# PWM_Regenerator.net
KiCad netlist of a schematic drawn in Altium Designer
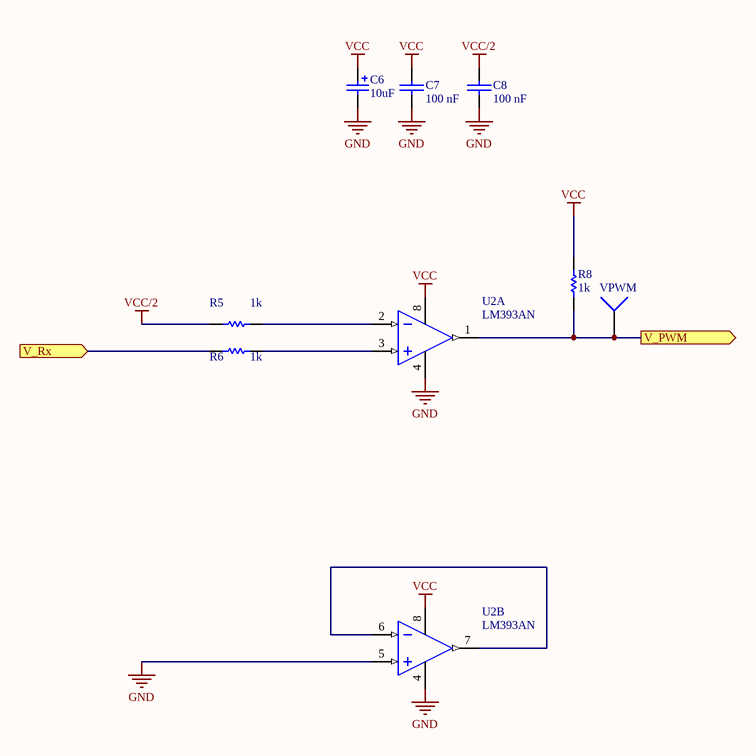
[diagram p0: PWM Regenerator.SchDoc]

(export (version "E")
  (design (tool "Eeschema 10.0.6"))
  (components
    (comp (ref "C6")
      (value "10uF")
      (footprint "ece-CAPAD2TH0.3")
      (description "Polarized Capacitor (Radial)")
      (fields (field (name "MANUFACTURER") "Generic Components") (field (name "PUBLISHER") "Altium Limited"))
      (libsource (lib "ece components") (part "CAP 22uF TH"))
    )
    (comp (ref "C7")
      (value "100 nF")
      (footprint "ece-RAD0.2")
      (description "Capacitor Non Polarised Through Hole")
      (libsource (lib "ece components") (part "CAP"))
    )
    (comp (ref "C8")
      (value "100 nF")
      (footprint "ece-RAD0.2")
      (description "Capacitor Non Polarised Through Hole")
      (libsource (lib "ece components") (part "CAP"))
    )
    (comp (ref "R5")
      (value "1k")
      (footprint "ece-AXIAL0.4")
      (description "Resistor")
      (fields (field (name "PUBLISHER") "Altium Limited"))
      (libsource (lib "ece components") (part "Res1"))
    )
    (comp (ref "R6")
      (value "1k")
      (footprint "ece-AXIAL0.4")
      (description "Resistor")
      (fields (field (name "PUBLISHER") "Altium Limited"))
      (libsource (lib "ece components") (part "Res1"))
    )
    (comp (ref "R8")
      (value "1k")
      (footprint "ece-AXIAL0.4")
      (description "Resistor")
      (fields (field (name "PUBLISHER") "Altium Limited"))
      (libsource (lib "ece components") (part "Res1"))
    )
    (comp (ref "U2")
      (value "LM393AN")
      (footprint "ECE-DIP8")
      (description "Dual Comparator")
      (fields (field (name "PUBLISHER") "Altium Limited"))
      (libsource (lib "ece components") (part "LM393AN"))
    )
    (comp (ref "VPWM")
      (value "VPWM")
      (footprint "ece-HDR1")
      (description "Socket")
      (fields (field (name "PUBLISHER") "Altium Limited"))
      (libsource (lib "ece components") (part "Test pin"))
    )
  )
  (nets
    (net (code "1") (name "/V_PWM") (class "Default")
      (node (ref "R8") (pin "1") (pinfunction "1_1") (pintype "passive"))
      (node (ref "U2") (pin "1") (pinfunction "OUT_1") (pintype "output"))
      (node (ref "VPWM") (pin "1") (pinfunction "1_1") (pintype "passive"))
    )
    (net (code "2") (name "/V_Rx") (class "Default")
      (node (ref "R6") (pin "1") (pinfunction "1_1") (pintype "passive"))
    )
    (net (code "3") (name "GND") (class "Default")
      (node (ref "C6") (pin "2") (pinfunction "2_2") (pintype "passive"))
      (node (ref "C7") (pin "2") (pinfunction "2_2") (pintype "passive"))
      (node (ref "C8") (pin "2") (pinfunction "2_2") (pintype "passive"))
      (node (ref "U2") (pin "4") (pinfunction "GND_4") (pintype "power_in"))
      (node (ref "U2") (pin "5") (pinfunction "IN+_5") (pintype "input"))
    )
    (net (code "4") (name "Net-(U2A-IN+)") (class "Default")
      (node (ref "R6") (pin "2") (pinfunction "2_2") (pintype "passive"))
      (node (ref "U2") (pin "3") (pinfunction "IN+_3") (pintype "input"))
    )
    (net (code "5") (name "Net-(U2A-IN-)") (class "Default")
      (node (ref "R5") (pin "2") (pinfunction "2_2") (pintype "passive"))
      (node (ref "U2") (pin "2") (pinfunction "IN-_2") (pintype "input"))
    )
    (net (code "6") (name "Net-(U2B-IN-)") (class "Default")
      (node (ref "U2") (pin "6") (pinfunction "IN-_6") (pintype "input"))
      (node (ref "U2") (pin "7") (pinfunction "OUT_7") (pintype "output"))
    )
    (net (code "7") (name "VCC") (class "Default")
      (node (ref "C6") (pin "1") (pinfunction "1_1") (pintype "passive"))
      (node (ref "C7") (pin "1") (pinfunction "1_1") (pintype "passive"))
      (node (ref "R8") (pin "2") (pinfunction "2_2") (pintype "passive"))
      (node (ref "U2") (pin "8") (pinfunction "V+_8") (pintype "power_in"))
    )
    (net (code "8") (name "VCC{slash}2") (class "Default")
      (node (ref "C8") (pin "1") (pinfunction "1_1") (pintype "passive"))
      (node (ref "R5") (pin "1") (pinfunction "1_1") (pintype "passive"))
    )
  )
)
